# 16_Vibrationdriver_PCA9685.net
KiCad netlist of a schematic drawn in EAGLE
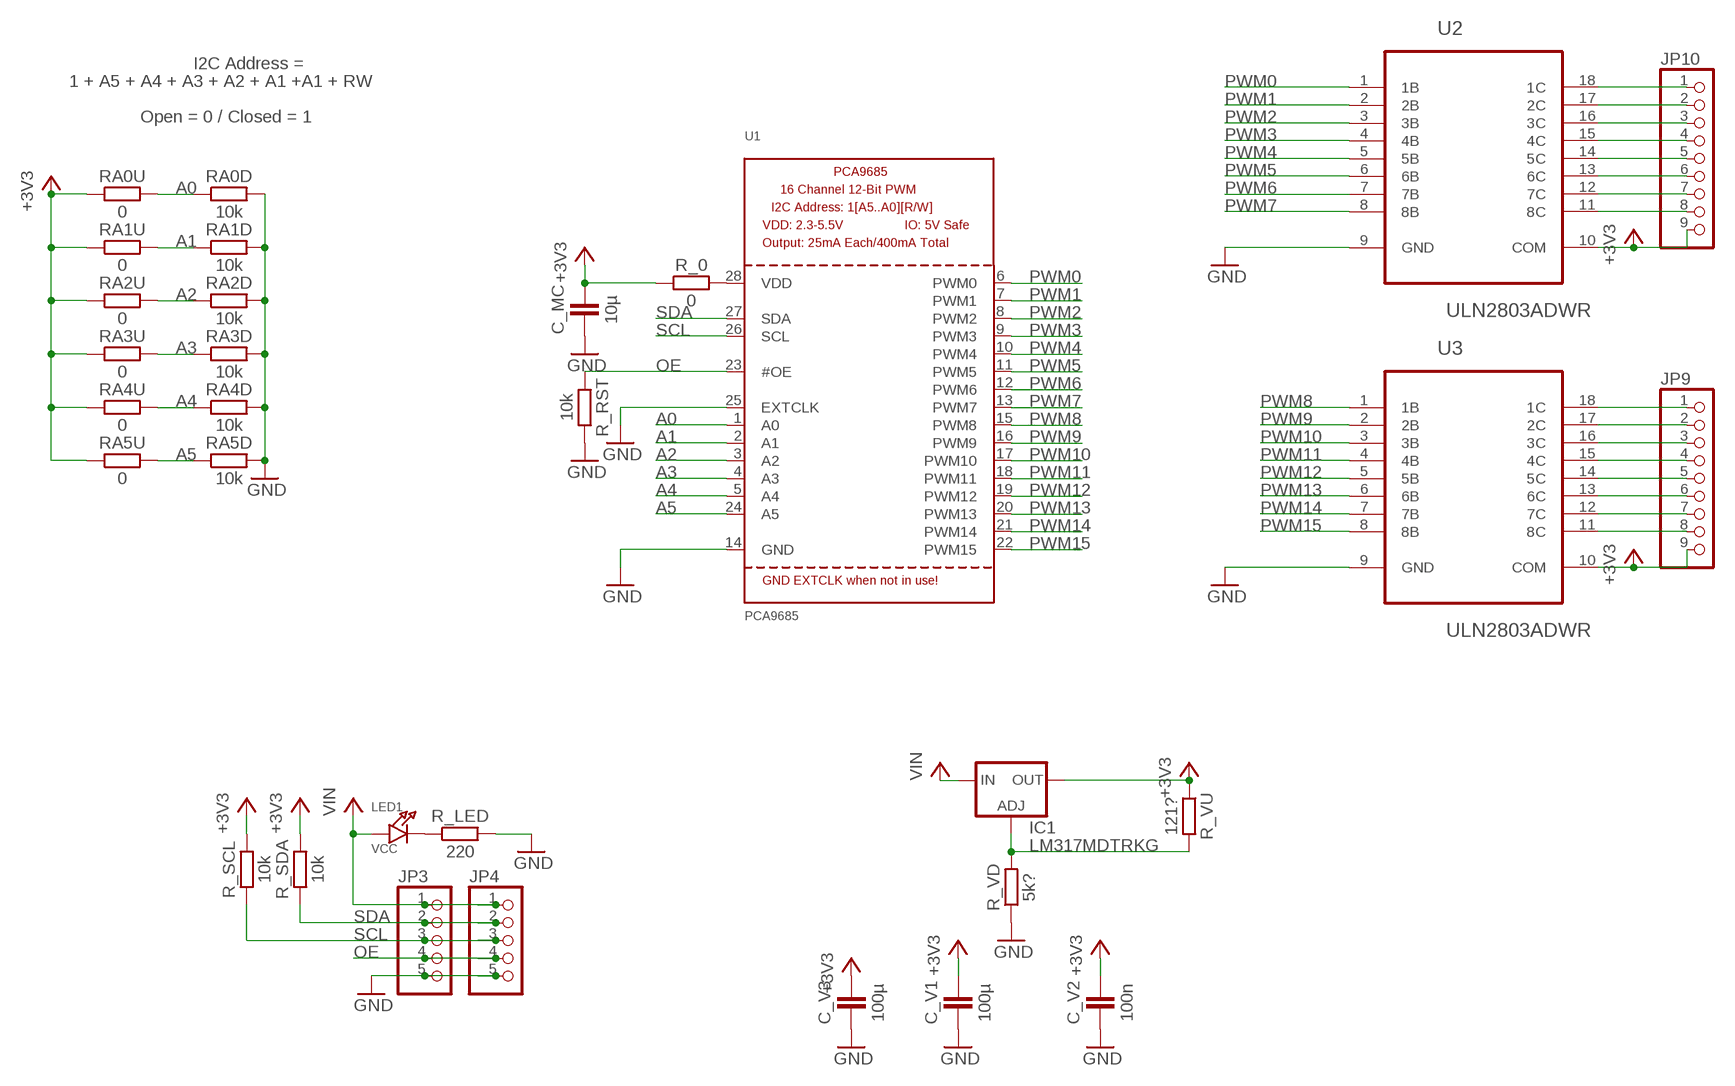
[diagram p0: schematic, sheet 1]

(export (version "E")
  (design (tool "Eeschema 10.0.6"))
  (components
    (comp (ref "C_MC")
      (value "10µ")
      (footprint "eagle-import:603")
      (libsource (lib "eagle-import") (part "CAPACITOR"))
    )
    (comp (ref "C_V1")
      (value "100µ")
      (footprint "eagle-import:1206")
      (libsource (lib "eagle-import") (part "CAPACITOR1206"))
    )
    (comp (ref "C_V2")
      (value "100n")
      (footprint "eagle-import:603")
      (libsource (lib "eagle-import") (part "CAPACITOR"))
    )
    (comp (ref "C_V3")
      (value "100µ")
      (footprint "eagle-import:1206")
      (libsource (lib "eagle-import") (part "CAPACITOR1206"))
    )
    (comp (ref "IC1")
      (value "LM317MDTRKG")
      (footprint "eagle-import:DPACK")
      (libsource (lib "eagle-import") (part "LM317?MDTRKG"))
    )
    (comp (ref "JP3")
      (value "PINHD-1X5")
      (footprint "eagle-import:1X05")
      (libsource (lib "eagle-import") (part "PINHD-1X5"))
    )
    (comp (ref "JP4")
      (value "PINHD-1X5")
      (footprint "eagle-import:1X05")
      (libsource (lib "eagle-import") (part "PINHD-1X5"))
    )
    (comp (ref "JP9")
      (value "PINHD-1X9")
      (footprint "eagle-import:1X09")
      (libsource (lib "eagle-import") (part "PINHD-1X9"))
    )
    (comp (ref "JP10")
      (value "PINHD-1X9")
      (footprint "eagle-import:1X09")
      (libsource (lib "eagle-import") (part "PINHD-1X9"))
    )
    (comp (ref "LED1")
      (value "VCC")
      (footprint "eagle-import:CHIPLED_0805")
      (libsource (lib "eagle-import") (part "LED0805"))
    )
    (comp (ref "RA0D")
      (value "10k")
      (footprint "eagle-import:603")
      (libsource (lib "eagle-import") (part "RESISTOR0603"))
    )
    (comp (ref "RA0U")
      (value "0")
      (footprint "eagle-import:603")
      (libsource (lib "eagle-import") (part "RESISTOR0603"))
    )
    (comp (ref "RA1D")
      (value "10k")
      (footprint "eagle-import:603")
      (libsource (lib "eagle-import") (part "RESISTOR0603"))
    )
    (comp (ref "RA1U")
      (value "0")
      (footprint "eagle-import:603")
      (libsource (lib "eagle-import") (part "RESISTOR0603"))
    )
    (comp (ref "RA2D")
      (value "10k")
      (footprint "eagle-import:603")
      (libsource (lib "eagle-import") (part "RESISTOR0603"))
    )
    (comp (ref "RA2U")
      (value "0")
      (footprint "eagle-import:603")
      (libsource (lib "eagle-import") (part "RESISTOR0603"))
    )
    (comp (ref "RA3D")
      (value "10k")
      (footprint "eagle-import:603")
      (libsource (lib "eagle-import") (part "RESISTOR0603"))
    )
    (comp (ref "RA3U")
      (value "0")
      (footprint "eagle-import:603")
      (libsource (lib "eagle-import") (part "RESISTOR0603"))
    )
    (comp (ref "RA4D")
      (value "10k")
      (footprint "eagle-import:603")
      (libsource (lib "eagle-import") (part "RESISTOR0603"))
    )
    (comp (ref "RA4U")
      (value "0")
      (footprint "eagle-import:603")
      (libsource (lib "eagle-import") (part "RESISTOR0603"))
    )
    (comp (ref "RA5D")
      (value "10k")
      (footprint "eagle-import:603")
      (libsource (lib "eagle-import") (part "RESISTOR0603"))
    )
    (comp (ref "RA5U")
      (value "0")
      (footprint "eagle-import:603")
      (libsource (lib "eagle-import") (part "RESISTOR0603"))
    )
    (comp (ref "R_0")
      (value "0")
      (footprint "eagle-import:603")
      (libsource (lib "eagle-import") (part "RESISTOR0603"))
    )
    (comp (ref "R_LED")
      (value "220")
      (footprint "eagle-import:603")
      (libsource (lib "eagle-import") (part "RESISTOR0603"))
    )
    (comp (ref "R_RST")
      (value "10k")
      (footprint "eagle-import:603")
      (libsource (lib "eagle-import") (part "RESISTOR0603"))
    )
    (comp (ref "R_SCL")
      (value "10k")
      (footprint "eagle-import:603")
      (libsource (lib "eagle-import") (part "RESISTOR0603"))
    )
    (comp (ref "R_SDA")
      (value "10k")
      (footprint "eagle-import:603")
      (libsource (lib "eagle-import") (part "RESISTOR0603"))
    )
    (comp (ref "R_VD")
      (value "5k?")
      (footprint "eagle-import:603")
      (libsource (lib "eagle-import") (part "RESISTOR0603"))
    )
    (comp (ref "R_VU")
      (value "121?")
      (footprint "eagle-import:603")
      (libsource (lib "eagle-import") (part "RESISTOR0603"))
    )
    (comp (ref "U1")
      (value "PCA9685")
      (footprint "eagle-import:TSSOP28")
      (libsource (lib "eagle-import") (part "PCA9685"))
    )
    (comp (ref "U2")
      (value "ULN2803ADWR")
      (footprint "eagle-import:SOIC127P1030X265-18N")
      (libsource (lib "eagle-import") (part "ULN2803ADWR"))
    )
    (comp (ref "U3")
      (value "ULN2803ADWR")
      (footprint "eagle-import:SOIC127P1030X265-18N")
      (libsource (lib "eagle-import") (part "ULN2803ADWR"))
    )
  )
  (nets
    (net (code "1") (name "+3V3") (class "Default")
      (node (ref "C_MC") (pin "2") (pinfunction "2_2") (pintype "passive"))
      (node (ref "C_V1") (pin "2") (pinfunction "2_2") (pintype "passive"))
      (node (ref "C_V2") (pin "2") (pinfunction "2_2") (pintype "passive"))
      (node (ref "C_V3") (pin "2") (pinfunction "2_2") (pintype "passive"))
      (node (ref "IC1") (pin "4") (pinfunction "OUT_4") (pintype "passive"))
      (node (ref "JP10") (pin "9") (pinfunction "9_9") (pintype "passive"))
      (node (ref "JP9") (pin "9") (pinfunction "9_9") (pintype "passive"))
      (node (ref "RA0U") (pin "1") (pinfunction "1_1") (pintype "passive"))
      (node (ref "RA1U") (pin "1") (pinfunction "1_1") (pintype "passive"))
      (node (ref "RA2U") (pin "1") (pinfunction "1_1") (pintype "passive"))
      (node (ref "RA3U") (pin "1") (pinfunction "1_1") (pintype "passive"))
      (node (ref "RA4U") (pin "1") (pinfunction "1_1") (pintype "passive"))
      (node (ref "RA5U") (pin "1") (pinfunction "1_1") (pintype "passive"))
      (node (ref "R_0") (pin "1") (pinfunction "1_1") (pintype "passive"))
      (node (ref "R_SCL") (pin "2") (pinfunction "2_2") (pintype "passive"))
      (node (ref "R_SDA") (pin "2") (pinfunction "2_2") (pintype "passive"))
      (node (ref "R_VU") (pin "1") (pinfunction "1_1") (pintype "passive"))
      (node (ref "U2") (pin "10") (pinfunction "COM_10") (pintype "output"))
      (node (ref "U3") (pin "10") (pinfunction "COM_10") (pintype "output"))
    )
    (net (code "2") (name "/A0") (class "Default")
      (node (ref "RA0D") (pin "1") (pinfunction "1_1") (pintype "passive"))
      (node (ref "RA0U") (pin "2") (pinfunction "2_2") (pintype "passive"))
      (node (ref "U1") (pin "1") (pinfunction "A0_1") (pintype "bidirectional"))
    )
    (net (code "3") (name "/A1") (class "Default")
      (node (ref "RA1D") (pin "1") (pinfunction "1_1") (pintype "passive"))
      (node (ref "RA1U") (pin "2") (pinfunction "2_2") (pintype "passive"))
      (node (ref "U1") (pin "2") (pinfunction "A1_2") (pintype "bidirectional"))
    )
    (net (code "4") (name "/A2") (class "Default")
      (node (ref "RA2D") (pin "1") (pinfunction "1_1") (pintype "passive"))
      (node (ref "RA2U") (pin "2") (pinfunction "2_2") (pintype "passive"))
      (node (ref "U1") (pin "3") (pinfunction "A2_3") (pintype "bidirectional"))
    )
    (net (code "5") (name "/A3") (class "Default")
      (node (ref "RA3D") (pin "1") (pinfunction "1_1") (pintype "passive"))
      (node (ref "RA3U") (pin "2") (pinfunction "2_2") (pintype "passive"))
      (node (ref "U1") (pin "4") (pinfunction "A3_4") (pintype "bidirectional"))
    )
    (net (code "6") (name "/A4") (class "Default")
      (node (ref "RA4D") (pin "1") (pinfunction "1_1") (pintype "passive"))
      (node (ref "RA4U") (pin "2") (pinfunction "2_2") (pintype "passive"))
      (node (ref "U1") (pin "5") (pinfunction "A4_5") (pintype "bidirectional"))
    )
    (net (code "7") (name "/A5") (class "Default")
      (node (ref "RA5D") (pin "1") (pinfunction "1_1") (pintype "passive"))
      (node (ref "RA5U") (pin "2") (pinfunction "2_2") (pintype "passive"))
      (node (ref "U1") (pin "24") (pinfunction "A5_24") (pintype "bidirectional"))
    )
    (net (code "8") (name "/OE") (class "Default")
      (node (ref "JP3") (pin "4") (pinfunction "4_4") (pintype "passive"))
      (node (ref "JP4") (pin "4") (pinfunction "4_4") (pintype "passive"))
      (node (ref "R_RST") (pin "1") (pinfunction "1_1") (pintype "passive"))
      (node (ref "U1") (pin "23") (pinfunction "#OE_23") (pintype "input"))
    )
    (net (code "9") (name "/PWM0") (class "Default")
      (node (ref "U1") (pin "6") (pinfunction "PWM0_6") (pintype "output"))
      (node (ref "U2") (pin "1") (pinfunction "1B_1") (pintype "input"))
    )
    (net (code "10") (name "/PWM1") (class "Default")
      (node (ref "U1") (pin "7") (pinfunction "PWM1_7") (pintype "output"))
      (node (ref "U2") (pin "2") (pinfunction "2B_2") (pintype "input"))
    )
    (net (code "11") (name "/PWM2") (class "Default")
      (node (ref "U1") (pin "8") (pinfunction "PWM2_8") (pintype "output"))
      (node (ref "U2") (pin "3") (pinfunction "3B_3") (pintype "input"))
    )
    (net (code "12") (name "/PWM3") (class "Default")
      (node (ref "U1") (pin "9") (pinfunction "PWM3_9") (pintype "output"))
      (node (ref "U2") (pin "4") (pinfunction "4B_4") (pintype "input"))
    )
    (net (code "13") (name "/PWM4") (class "Default")
      (node (ref "U1") (pin "10") (pinfunction "PWM4_10") (pintype "output"))
      (node (ref "U2") (pin "5") (pinfunction "5B_5") (pintype "input"))
    )
    (net (code "14") (name "/PWM5") (class "Default")
      (node (ref "U1") (pin "11") (pinfunction "PWM5_11") (pintype "output"))
      (node (ref "U2") (pin "6") (pinfunction "6B_6") (pintype "input"))
    )
    (net (code "15") (name "/PWM6") (class "Default")
      (node (ref "U1") (pin "12") (pinfunction "PWM6_12") (pintype "output"))
      (node (ref "U2") (pin "7") (pinfunction "7B_7") (pintype "input"))
    )
    (net (code "16") (name "/PWM7") (class "Default")
      (node (ref "U1") (pin "13") (pinfunction "PWM7_13") (pintype "output"))
      (node (ref "U2") (pin "8") (pinfunction "8B_8") (pintype "input"))
    )
    (net (code "17") (name "/PWM8") (class "Default")
      (node (ref "U1") (pin "15") (pinfunction "PWM8_15") (pintype "output"))
      (node (ref "U3") (pin "1") (pinfunction "1B_1") (pintype "input"))
    )
    (net (code "18") (name "/PWM9") (class "Default")
      (node (ref "U1") (pin "16") (pinfunction "PWM9_16") (pintype "output"))
      (node (ref "U3") (pin "2") (pinfunction "2B_2") (pintype "input"))
    )
    (net (code "19") (name "/PWM10") (class "Default")
      (node (ref "U1") (pin "17") (pinfunction "PWM10_17") (pintype "output"))
      (node (ref "U3") (pin "3") (pinfunction "3B_3") (pintype "input"))
    )
    (net (code "20") (name "/PWM11") (class "Default")
      (node (ref "U1") (pin "18") (pinfunction "PWM11_18") (pintype "output"))
      (node (ref "U3") (pin "4") (pinfunction "4B_4") (pintype "input"))
    )
    (net (code "21") (name "/PWM12") (class "Default")
      (node (ref "U1") (pin "19") (pinfunction "PWM12_19") (pintype "output"))
      (node (ref "U3") (pin "5") (pinfunction "5B_5") (pintype "input"))
    )
    (net (code "22") (name "/PWM13") (class "Default")
      (node (ref "U1") (pin "20") (pinfunction "PWM13_20") (pintype "output"))
      (node (ref "U3") (pin "6") (pinfunction "6B_6") (pintype "input"))
    )
    (net (code "23") (name "/PWM14") (class "Default")
      (node (ref "U1") (pin "21") (pinfunction "PWM14_21") (pintype "output"))
      (node (ref "U3") (pin "7") (pinfunction "7B_7") (pintype "input"))
    )
    (net (code "24") (name "/PWM15") (class "Default")
      (node (ref "U1") (pin "22") (pinfunction "PWM15_22") (pintype "output"))
      (node (ref "U3") (pin "8") (pinfunction "8B_8") (pintype "input"))
    )
    (net (code "25") (name "/SCL") (class "Default")
      (node (ref "JP3") (pin "3") (pinfunction "3_3") (pintype "passive"))
      (node (ref "JP4") (pin "3") (pinfunction "3_3") (pintype "passive"))
      (node (ref "R_SCL") (pin "1") (pinfunction "1_1") (pintype "passive"))
      (node (ref "U1") (pin "26") (pinfunction "SCL_26") (pintype "bidirectional"))
    )
    (net (code "26") (name "/SDA") (class "Default")
      (node (ref "JP3") (pin "2") (pinfunction "2_2") (pintype "passive"))
      (node (ref "JP4") (pin "2") (pinfunction "2_2") (pintype "passive"))
      (node (ref "R_SDA") (pin "1") (pinfunction "1_1") (pintype "passive"))
      (node (ref "U1") (pin "27") (pinfunction "SDA_27") (pintype "bidirectional"))
    )
    (net (code "27") (name "GND") (class "Default")
      (node (ref "C_MC") (pin "1") (pinfunction "1_1") (pintype "passive"))
      (node (ref "C_V1") (pin "1") (pinfunction "1_1") (pintype "passive"))
      (node (ref "C_V2") (pin "1") (pinfunction "1_1") (pintype "passive"))
      (node (ref "C_V3") (pin "1") (pinfunction "1_1") (pintype "passive"))
      (node (ref "JP3") (pin "5") (pinfunction "5_5") (pintype "passive"))
      (node (ref "JP4") (pin "5") (pinfunction "5_5") (pintype "passive"))
      (node (ref "RA0D") (pin "2") (pinfunction "2_2") (pintype "passive"))
      (node (ref "RA1D") (pin "2") (pinfunction "2_2") (pintype "passive"))
      (node (ref "RA2D") (pin "2") (pinfunction "2_2") (pintype "passive"))
      (node (ref "RA3D") (pin "2") (pinfunction "2_2") (pintype "passive"))
      (node (ref "RA4D") (pin "2") (pinfunction "2_2") (pintype "passive"))
      (node (ref "RA5D") (pin "2") (pinfunction "2_2") (pintype "passive"))
      (node (ref "R_LED") (pin "2") (pinfunction "2_2") (pintype "passive"))
      (node (ref "R_RST") (pin "2") (pinfunction "2_2") (pintype "passive"))
      (node (ref "R_VD") (pin "1") (pinfunction "1_1") (pintype "passive"))
      (node (ref "U1") (pin "14") (pinfunction "GND_14") (pintype "power_in"))
      (node (ref "U1") (pin "25") (pinfunction "EXTCLK_25") (pintype "input"))
      (node (ref "U2") (pin "9") (pinfunction "GND_9") (pintype "passive"))
      (node (ref "U3") (pin "9") (pinfunction "GND_9") (pintype "passive"))
    )
    (net (code "28") (name "Net-(IC1-ADJ)") (class "Default")
      (node (ref "IC1") (pin "1") (pinfunction "ADJ_1") (pintype "input"))
      (node (ref "R_VD") (pin "2") (pinfunction "2_2") (pintype "passive"))
      (node (ref "R_VU") (pin "2") (pinfunction "2_2") (pintype "passive"))
    )
    (net (code "29") (name "Net-(LED1-PadC)") (class "Default")
      (node (ref "LED1") (pin "C") (pinfunction "C_C") (pintype "passive"))
      (node (ref "R_LED") (pin "1") (pinfunction "1_1") (pintype "passive"))
    )
    (net (code "30") (name "Net-(U1-VDD)") (class "Default")
      (node (ref "R_0") (pin "2") (pinfunction "2_2") (pintype "passive"))
      (node (ref "U1") (pin "28") (pinfunction "VDD_28") (pintype "power_in"))
    )
    (net (code "31") (name "Net-(U2-1C)") (class "Default")
      (node (ref "JP10") (pin "1") (pinfunction "1_1") (pintype "passive"))
      (node (ref "U2") (pin "18") (pinfunction "1C_18") (pintype "output"))
    )
    (net (code "32") (name "Net-(U2-2C)") (class "Default")
      (node (ref "JP10") (pin "2") (pinfunction "2_2") (pintype "passive"))
      (node (ref "U2") (pin "17") (pinfunction "2C_17") (pintype "output"))
    )
    (net (code "33") (name "Net-(U2-3C)") (class "Default")
      (node (ref "JP10") (pin "3") (pinfunction "3_3") (pintype "passive"))
      (node (ref "U2") (pin "16") (pinfunction "3C_16") (pintype "output"))
    )
    (net (code "34") (name "Net-(U2-4C)") (class "Default")
      (node (ref "JP10") (pin "4") (pinfunction "4_4") (pintype "passive"))
      (node (ref "U2") (pin "15") (pinfunction "4C_15") (pintype "output"))
    )
    (net (code "35") (name "Net-(U2-5C)") (class "Default")
      (node (ref "JP10") (pin "5") (pinfunction "5_5") (pintype "passive"))
      (node (ref "U2") (pin "14") (pinfunction "5C_14") (pintype "output"))
    )
    (net (code "36") (name "Net-(U2-6C)") (class "Default")
      (node (ref "JP10") (pin "6") (pinfunction "6_6") (pintype "passive"))
      (node (ref "U2") (pin "13") (pinfunction "6C_13") (pintype "output"))
    )
    (net (code "37") (name "Net-(U2-7C)") (class "Default")
      (node (ref "JP10") (pin "7") (pinfunction "7_7") (pintype "passive"))
      (node (ref "U2") (pin "12") (pinfunction "7C_12") (pintype "output"))
    )
    (net (code "38") (name "Net-(U2-8C)") (class "Default")
      (node (ref "JP10") (pin "8") (pinfunction "8_8") (pintype "passive"))
      (node (ref "U2") (pin "11") (pinfunction "8C_11") (pintype "output"))
    )
    (net (code "39") (name "Net-(U3-1C)") (class "Default")
      (node (ref "JP9") (pin "1") (pinfunction "1_1") (pintype "passive"))
      (node (ref "U3") (pin "18") (pinfunction "1C_18") (pintype "output"))
    )
    (net (code "40") (name "Net-(U3-2C)") (class "Default")
      (node (ref "JP9") (pin "2") (pinfunction "2_2") (pintype "passive"))
      (node (ref "U3") (pin "17") (pinfunction "2C_17") (pintype "output"))
    )
    (net (code "41") (name "Net-(U3-3C)") (class "Default")
      (node (ref "JP9") (pin "3") (pinfunction "3_3") (pintype "passive"))
      (node (ref "U3") (pin "16") (pinfunction "3C_16") (pintype "output"))
    )
    (net (code "42") (name "Net-(U3-4C)") (class "Default")
      (node (ref "JP9") (pin "4") (pinfunction "4_4") (pintype "passive"))
      (node (ref "U3") (pin "15") (pinfunction "4C_15") (pintype "output"))
    )
    (net (code "43") (name "Net-(U3-5C)") (class "Default")
      (node (ref "JP9") (pin "5") (pinfunction "5_5") (pintype "passive"))
      (node (ref "U3") (pin "14") (pinfunction "5C_14") (pintype "output"))
    )
    (net (code "44") (name "Net-(U3-6C)") (class "Default")
      (node (ref "JP9") (pin "6") (pinfunction "6_6") (pintype "passive"))
      (node (ref "U3") (pin "13") (pinfunction "6C_13") (pintype "output"))
    )
    (net (code "45") (name "Net-(U3-7C)") (class "Default")
      (node (ref "JP9") (pin "7") (pinfunction "7_7") (pintype "passive"))
      (node (ref "U3") (pin "12") (pinfunction "7C_12") (pintype "output"))
    )
    (net (code "46") (name "Net-(U3-8C)") (class "Default")
      (node (ref "JP9") (pin "8") (pinfunction "8_8") (pintype "passive"))
      (node (ref "U3") (pin "11") (pinfunction "8C_11") (pintype "output"))
    )
    (net (code "47") (name "VIN") (class "Default")
      (node (ref "IC1") (pin "3") (pinfunction "IN_3") (pintype "input"))
      (node (ref "JP3") (pin "1") (pinfunction "1_1") (pintype "passive"))
      (node (ref "JP4") (pin "1") (pinfunction "1_1") (pintype "passive"))
      (node (ref "LED1") (pin "A") (pinfunction "A_A") (pintype "passive"))
    )
  )
)
